# ATmega168Led.net
KiCad netlist of a schematic drawn in EAGLE
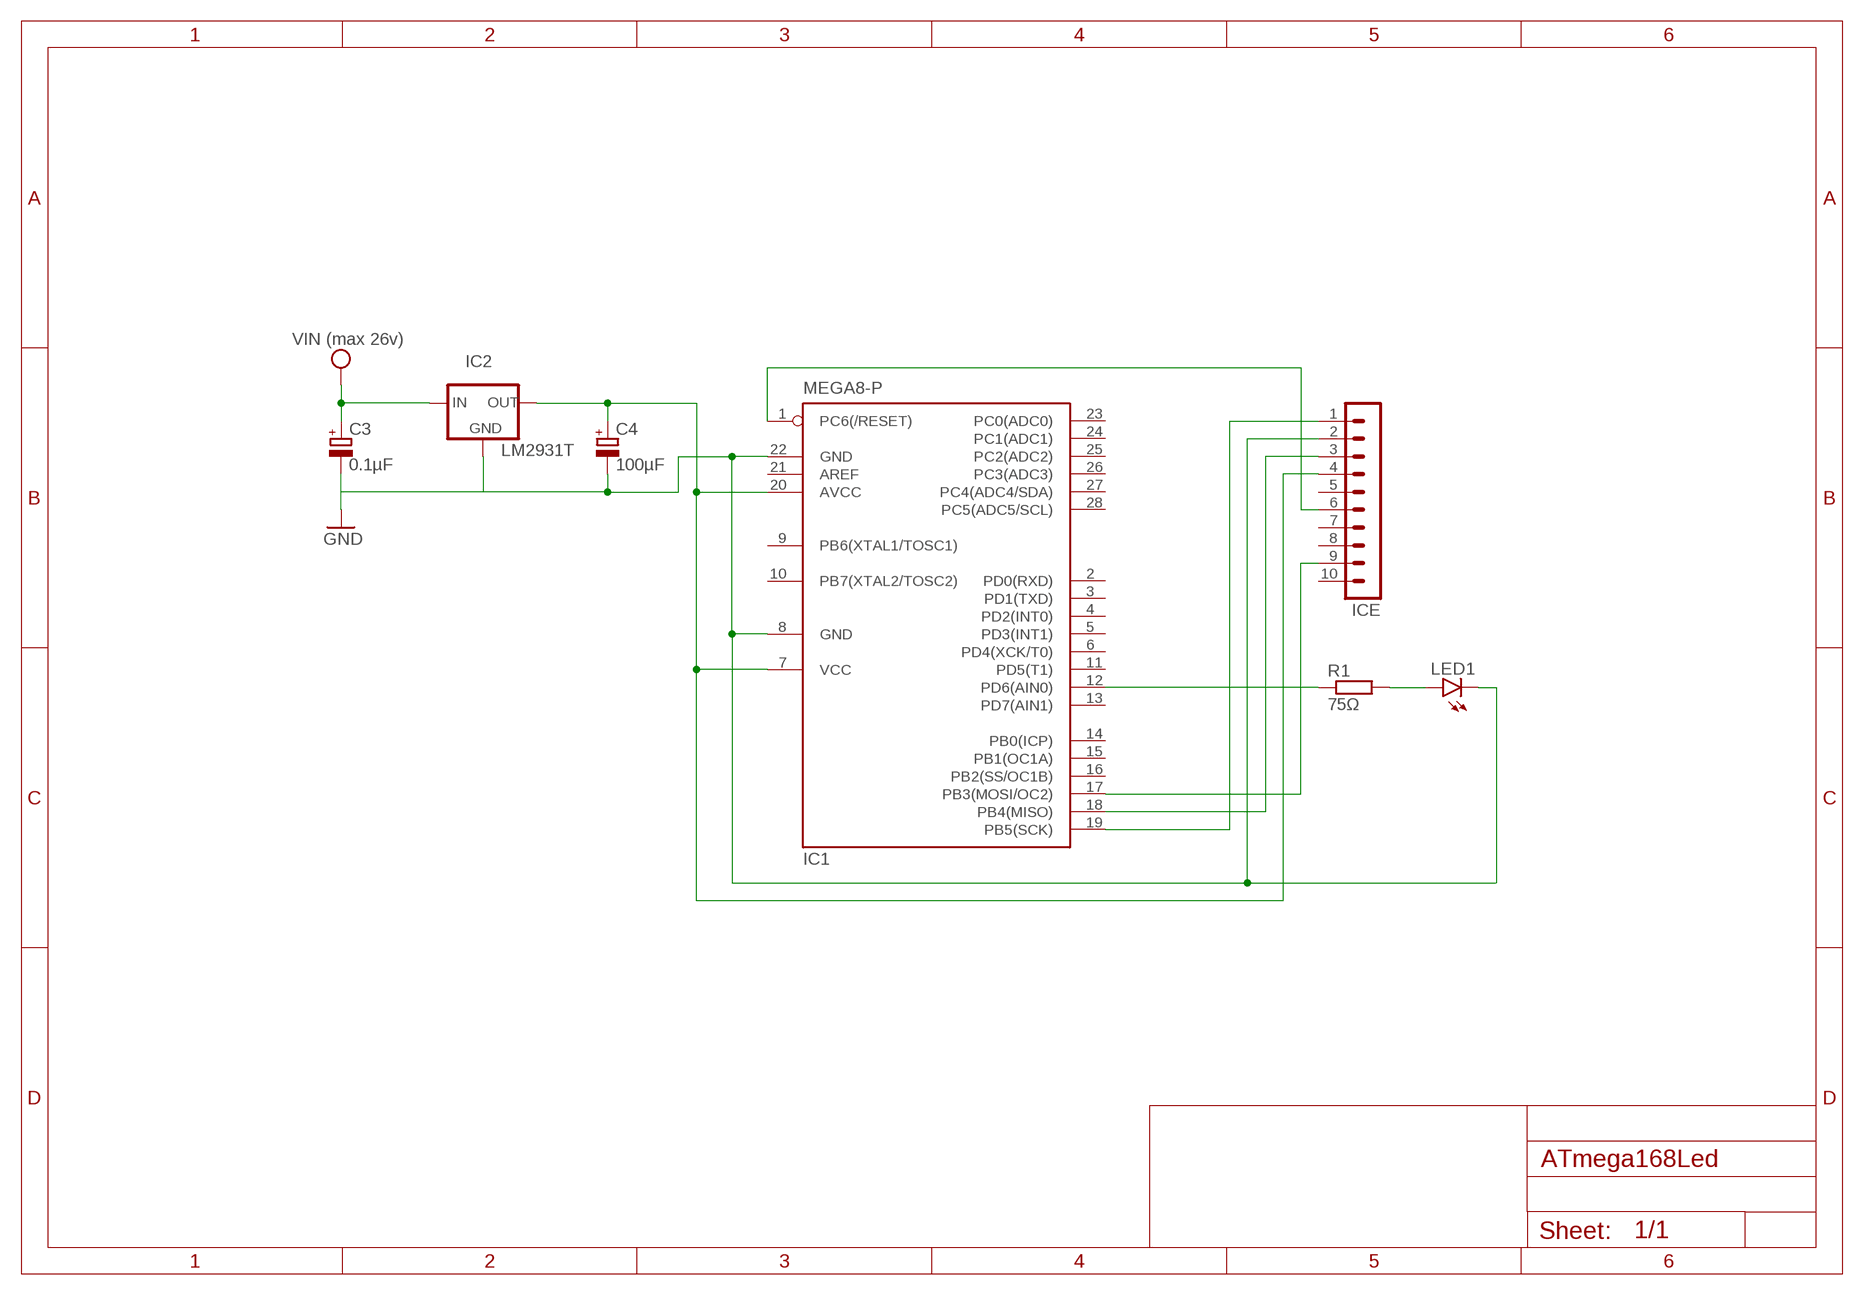
[diagram p0: schematic, sheet 1]

(export (version "E")
  (design (tool "Eeschema 10.0.6"))
  (components
    (comp (ref "C3")
      (value "0.1µF")
      (footprint "eagle-import:E5-5")
      (libsource (lib "eagle-import") (part "CPOL-EUE5-5"))
    )
    (comp (ref "C4")
      (value "100µF")
      (footprint "eagle-import:E5-5")
      (libsource (lib "eagle-import") (part "CPOL-EUE5-5"))
    )
    (comp (ref "IC1")
      (value "MEGA8-P")
      (footprint "eagle-import:DIL28-3")
      (libsource (lib "eagle-import") (part "MEGA8-P"))
    )
    (comp (ref "IC2")
      (value "LM2931T")
      (footprint "eagle-import:TO220S")
      (libsource (lib "eagle-import") (part "LM2931T"))
    )
    (comp (ref "ICE")
      (value "MA10-1")
      (footprint "eagle-import:MA10-1")
      (libsource (lib "eagle-import") (part "MA10-1"))
    )
    (comp (ref "LED1")
      (value "SFH482")
      (footprint "eagle-import:SFH482")
      (libsource (lib "eagle-import") (part "SFH482"))
    )
    (comp (ref "R1")
      (value "75Ω")
      (footprint "eagle-import:0617_17")
      (libsource (lib "eagle-import") (part "R-EU_0617/17"))
    )
  )
  (nets
    (net (code "1") (name "GND") (class "Default")
      (node (ref "C3") (pin "-") (pinfunction "-_-") (pintype "passive"))
      (node (ref "C4") (pin "-") (pinfunction "-_-") (pintype "passive"))
      (node (ref "IC1") (pin "22") (pinfunction "GND_22") (pintype "power_in"))
      (node (ref "IC1") (pin "8") (pinfunction "GND_8") (pintype "power_in"))
      (node (ref "IC2") (pin "2") (pinfunction "GND_2") (pintype "input"))
      (node (ref "ICE") (pin "2") (pinfunction "2_2") (pintype "passive"))
      (node (ref "LED1") (pin "K") (pinfunction "C_K") (pintype "passive"))
    )
    (net (code "2") (name "Net-(IC1-AVCC)") (class "Default")
      (node (ref "C4") (pin "+") (pinfunction "+_+") (pintype "passive"))
      (node (ref "IC1") (pin "20") (pinfunction "AVCC_20") (pintype "power_in"))
      (node (ref "IC1") (pin "7") (pinfunction "VCC_7") (pintype "power_in"))
      (node (ref "IC2") (pin "3") (pinfunction "OUT_3") (pintype "passive"))
      (node (ref "ICE") (pin "4") (pinfunction "4_4") (pintype "passive"))
    )
    (net (code "3") (name "Net-(IC1-PB3(MOSI{slash}OC2))") (class "Default")
      (node (ref "IC1") (pin "17") (pinfunction "PB3(MOSI/OC2)_17") (pintype "bidirectional"))
      (node (ref "ICE") (pin "9") (pinfunction "9_9") (pintype "passive"))
    )
    (net (code "4") (name "Net-(IC1-PB4(MISO))") (class "Default")
      (node (ref "IC1") (pin "18") (pinfunction "PB4(MISO)_18") (pintype "bidirectional"))
      (node (ref "ICE") (pin "3") (pinfunction "3_3") (pintype "passive"))
    )
    (net (code "5") (name "Net-(IC1-PB5(SCK))") (class "Default")
      (node (ref "IC1") (pin "19") (pinfunction "PB5(SCK)_19") (pintype "bidirectional"))
      (node (ref "ICE") (pin "1") (pinfunction "1_1") (pintype "passive"))
    )
    (net (code "6") (name "Net-(IC1-PC6({slash}RESET))") (class "Default")
      (node (ref "IC1") (pin "1") (pinfunction "PC6(/RESET)_1") (pintype "bidirectional"))
      (node (ref "ICE") (pin "6") (pinfunction "6_6") (pintype "passive"))
    )
    (net (code "7") (name "Net-(IC1-PD6(AIN0))") (class "Default")
      (node (ref "IC1") (pin "12") (pinfunction "PD6(AIN0)_12") (pintype "bidirectional"))
      (node (ref "R1") (pin "1") (pinfunction "1_1") (pintype "passive"))
    )
    (net (code "8") (name "Net-(LED1-PadA)") (class "Default")
      (node (ref "LED1") (pin "A") (pinfunction "A_A") (pintype "passive"))
      (node (ref "R1") (pin "2") (pinfunction "2_2") (pintype "passive"))
    )
    (net (code "9") (name "VIN (max 26v)") (class "Default")
      (node (ref "C3") (pin "+") (pinfunction "+_+") (pintype "passive"))
      (node (ref "IC2") (pin "1") (pinfunction "IN_1") (pintype "input"))
    )
    (net (code "10") (name "unconnected-(IC1-AREF-Pad21)") (class "Default")
      (node (ref "IC1") (pin "21") (pinfunction "AREF_21") (pintype "passive"))
    )
    (net (code "11") (name "unconnected-(IC1-PB0(ICP)-Pad14)") (class "Default")
      (node (ref "IC1") (pin "14") (pinfunction "PB0(ICP)_14") (pintype "bidirectional"))
    )
    (net (code "12") (name "unconnected-(IC1-PB1(OC1A)-Pad15)") (class "Default")
      (node (ref "IC1") (pin "15") (pinfunction "PB1(OC1A)_15") (pintype "bidirectional"))
    )
    (net (code "13") (name "unconnected-(IC1-PB2(SS{slash}OC1B)-Pad16)") (class "Default")
      (node (ref "IC1") (pin "16") (pinfunction "PB2(SS/OC1B)_16") (pintype "bidirectional"))
    )
    (net (code "14") (name "unconnected-(IC1-PB6(XTAL1{slash}TOSC1)-Pad9)") (class "Default")
      (node (ref "IC1") (pin "9") (pinfunction "PB6(XTAL1/TOSC1)_9") (pintype "bidirectional"))
    )
    (net (code "15") (name "unconnected-(IC1-PB7(XTAL2{slash}TOSC2)-Pad10)") (class "Default")
      (node (ref "IC1") (pin "10") (pinfunction "PB7(XTAL2/TOSC2)_10") (pintype "bidirectional"))
    )
    (net (code "16") (name "unconnected-(IC1-PC0(ADC0)-Pad23)") (class "Default")
      (node (ref "IC1") (pin "23") (pinfunction "PC0(ADC0)_23") (pintype "bidirectional"))
    )
    (net (code "17") (name "unconnected-(IC1-PC1(ADC1)-Pad24)") (class "Default")
      (node (ref "IC1") (pin "24") (pinfunction "PC1(ADC1)_24") (pintype "bidirectional"))
    )
    (net (code "18") (name "unconnected-(IC1-PC2(ADC2)-Pad25)") (class "Default")
      (node (ref "IC1") (pin "25") (pinfunction "PC2(ADC2)_25") (pintype "bidirectional"))
    )
    (net (code "19") (name "unconnected-(IC1-PC3(ADC3)-Pad26)") (class "Default")
      (node (ref "IC1") (pin "26") (pinfunction "PC3(ADC3)_26") (pintype "bidirectional"))
    )
    (net (code "20") (name "unconnected-(IC1-PC4(ADC4{slash}SDA)-Pad27)") (class "Default")
      (node (ref "IC1") (pin "27") (pinfunction "PC4(ADC4/SDA)_27") (pintype "bidirectional"))
    )
    (net (code "21") (name "unconnected-(IC1-PC5(ADC5{slash}SCL)-Pad28)") (class "Default")
      (node (ref "IC1") (pin "28") (pinfunction "PC5(ADC5/SCL)_28") (pintype "bidirectional"))
    )
    (net (code "22") (name "unconnected-(IC1-PD0(RXD)-Pad2)") (class "Default")
      (node (ref "IC1") (pin "2") (pinfunction "PD0(RXD)_2") (pintype "bidirectional"))
    )
    (net (code "23") (name "unconnected-(IC1-PD1(TXD)-Pad3)") (class "Default")
      (node (ref "IC1") (pin "3") (pinfunction "PD1(TXD)_3") (pintype "bidirectional"))
    )
    (net (code "24") (name "unconnected-(IC1-PD2(INT0)-Pad4)") (class "Default")
      (node (ref "IC1") (pin "4") (pinfunction "PD2(INT0)_4") (pintype "bidirectional"))
    )
    (net (code "25") (name "unconnected-(IC1-PD3(INT1)-Pad5)") (class "Default")
      (node (ref "IC1") (pin "5") (pinfunction "PD3(INT1)_5") (pintype "bidirectional"))
    )
    (net (code "26") (name "unconnected-(IC1-PD4(XCK{slash}T0)-Pad6)") (class "Default")
      (node (ref "IC1") (pin "6") (pinfunction "PD4(XCK/T0)_6") (pintype "bidirectional"))
    )
    (net (code "27") (name "unconnected-(IC1-PD5(T1)-Pad11)") (class "Default")
      (node (ref "IC1") (pin "11") (pinfunction "PD5(T1)_11") (pintype "bidirectional"))
    )
    (net (code "28") (name "unconnected-(IC1-PD7(AIN1)-Pad13)") (class "Default")
      (node (ref "IC1") (pin "13") (pinfunction "PD7(AIN1)_13") (pintype "bidirectional"))
    )
    (net (code "29") (name "unconnected-(ICE-Pad5)") (class "Default")
      (node (ref "ICE") (pin "5") (pinfunction "5_5") (pintype "passive"))
    )
    (net (code "30") (name "unconnected-(ICE-Pad7)") (class "Default")
      (node (ref "ICE") (pin "7") (pinfunction "7_7") (pintype "passive"))
    )
    (net (code "31") (name "unconnected-(ICE-Pad8)") (class "Default")
      (node (ref "ICE") (pin "8") (pinfunction "8_8") (pintype "passive"))
    )
    (net (code "32") (name "unconnected-(ICE-Pad10)") (class "Default")
      (node (ref "ICE") (pin "10") (pinfunction "10_10") (pintype "passive"))
    )
  )
)
